# eight_neopixels.net
KiCad netlist of a schematic drawn in Altium Designer
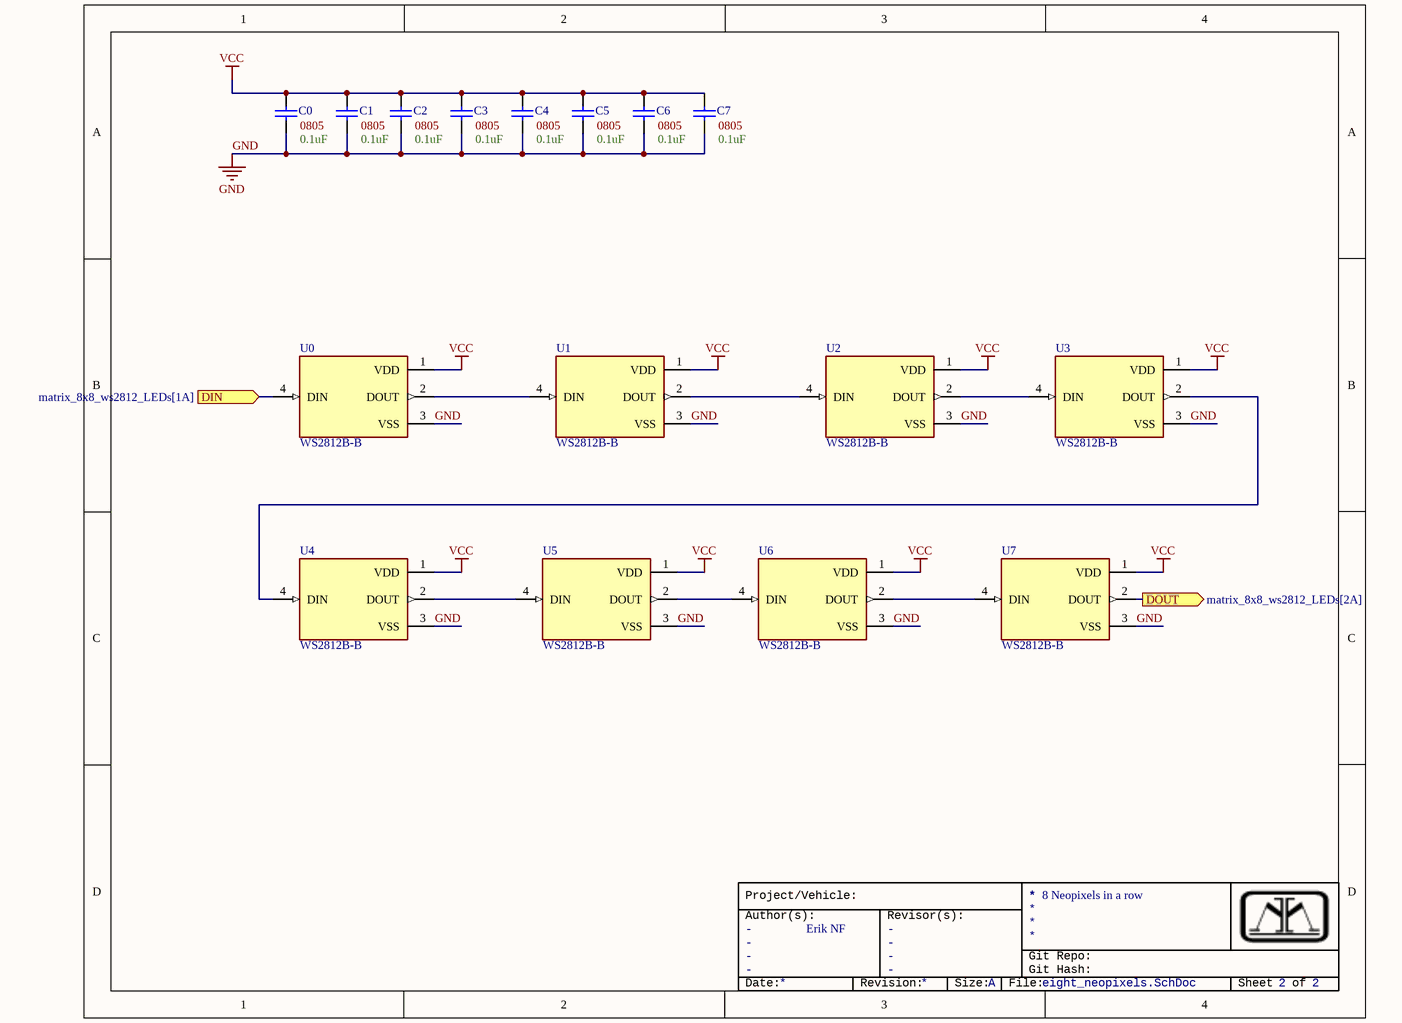
[diagram p0: eight_neopixels.SchDoc]

(export (version "E")
  (design (tool "Eeschema 10.0.6"))
  (components
    (comp (ref "C0")
      (value "SMD Nonpolarized")
      (footprint "[Cap] SMD 0805")
      (fields
        (field (name "VOLTAGE") "6.3V")
        (field (name "TOLERANCE") "10%")
        (field (name "SIZE PACKAGE") "0805")
        (field (name "CAPACITANCE") "0.1uF")
      )
      (libsource (lib "RADM Components") (part "[Cap] SMD Nonpolarized"))
    )
    (comp (ref "C1")
      (value "SMD Nonpolarized")
      (footprint "[Cap] SMD 0805")
      (fields
        (field (name "VOLTAGE") "6.3V")
        (field (name "TOLERANCE") "10%")
        (field (name "SIZE PACKAGE") "0805")
        (field (name "CAPACITANCE") "0.1uF")
      )
      (libsource (lib "RADM Components") (part "[Cap] SMD Nonpolarized"))
    )
    (comp (ref "C2")
      (value "SMD Nonpolarized")
      (footprint "[Cap] SMD 0805")
      (fields
        (field (name "VOLTAGE") "6.3V")
        (field (name "TOLERANCE") "10%")
        (field (name "SIZE PACKAGE") "0805")
        (field (name "CAPACITANCE") "0.1uF")
      )
      (libsource (lib "RADM Components") (part "[Cap] SMD Nonpolarized"))
    )
    (comp (ref "C3")
      (value "SMD Nonpolarized")
      (footprint "[Cap] SMD 0805")
      (fields
        (field (name "VOLTAGE") "6.3V")
        (field (name "TOLERANCE") "10%")
        (field (name "SIZE PACKAGE") "0805")
        (field (name "CAPACITANCE") "0.1uF")
      )
      (libsource (lib "RADM Components") (part "[Cap] SMD Nonpolarized"))
    )
    (comp (ref "C4")
      (value "SMD Nonpolarized")
      (footprint "[Cap] SMD 0805")
      (fields
        (field (name "VOLTAGE") "6.3V")
        (field (name "TOLERANCE") "10%")
        (field (name "SIZE PACKAGE") "0805")
        (field (name "CAPACITANCE") "0.1uF")
      )
      (libsource (lib "RADM Components") (part "[Cap] SMD Nonpolarized"))
    )
    (comp (ref "C5")
      (value "SMD Nonpolarized")
      (footprint "[Cap] SMD 0805")
      (fields
        (field (name "VOLTAGE") "6.3V")
        (field (name "TOLERANCE") "10%")
        (field (name "SIZE PACKAGE") "0805")
        (field (name "CAPACITANCE") "0.1uF")
      )
      (libsource (lib "RADM Components") (part "[Cap] SMD Nonpolarized"))
    )
    (comp (ref "C6")
      (value "SMD Nonpolarized")
      (footprint "[Cap] SMD 0805")
      (fields
        (field (name "VOLTAGE") "6.3V")
        (field (name "TOLERANCE") "10%")
        (field (name "SIZE PACKAGE") "0805")
        (field (name "CAPACITANCE") "0.1uF")
      )
      (libsource (lib "RADM Components") (part "[Cap] SMD Nonpolarized"))
    )
    (comp (ref "C7")
      (value "SMD Nonpolarized")
      (footprint "[Cap] SMD 0805")
      (fields
        (field (name "VOLTAGE") "6.3V")
        (field (name "TOLERANCE") "10%")
        (field (name "SIZE PACKAGE") "0805")
        (field (name "CAPACITANCE") "0.1uF")
      )
      (libsource (lib "RADM Components") (part "[Cap] SMD Nonpolarized"))
    )
    (comp (ref "U0")
      (value "WS2812B-B")
      (footprint "LED_WS2812B-B")
      (description "Intelligent control LED integrated light source")
      (libsource (lib "WS2812B-B") (part "WS2812B-B"))
    )
    (comp (ref "U1")
      (value "WS2812B-B")
      (footprint "LED_WS2812B-B")
      (description "Intelligent control LED integrated light source")
      (libsource (lib "WS2812B-B") (part "WS2812B-B"))
    )
    (comp (ref "U2")
      (value "WS2812B-B")
      (footprint "LED_WS2812B-B")
      (description "Intelligent control LED integrated light source")
      (libsource (lib "WS2812B-B") (part "WS2812B-B"))
    )
    (comp (ref "U3")
      (value "WS2812B-B")
      (footprint "LED_WS2812B-B")
      (description "Intelligent control LED integrated light source")
      (libsource (lib "WS2812B-B") (part "WS2812B-B"))
    )
    (comp (ref "U4")
      (value "WS2812B-B")
      (footprint "LED_WS2812B-B")
      (description "Intelligent control LED integrated light source")
      (libsource (lib "WS2812B-B") (part "WS2812B-B"))
    )
    (comp (ref "U5")
      (value "WS2812B-B")
      (footprint "LED_WS2812B-B")
      (description "Intelligent control LED integrated light source")
      (libsource (lib "WS2812B-B") (part "WS2812B-B"))
    )
    (comp (ref "U6")
      (value "WS2812B-B")
      (footprint "LED_WS2812B-B")
      (description "Intelligent control LED integrated light source")
      (libsource (lib "WS2812B-B") (part "WS2812B-B"))
    )
    (comp (ref "U7")
      (value "WS2812B-B")
      (footprint "LED_WS2812B-B")
      (description "Intelligent control LED integrated light source")
      (libsource (lib "WS2812B-B") (part "WS2812B-B"))
    )
  )
  (nets
    (net (code "1") (name "/DIN") (class "Default")
      (node (ref "U0") (pin "4") (pinfunction "DIN_4") (pintype "input"))
    )
    (net (code "2") (name "/DOUT") (class "Default")
      (node (ref "U7") (pin "2") (pinfunction "DOUT_2") (pintype "output"))
    )
    (net (code "3") (name "GND") (class "Default")
      (node (ref "C0") (pin "1") (pinfunction "1_1") (pintype "passive"))
      (node (ref "C1") (pin "1") (pinfunction "1_1") (pintype "passive"))
      (node (ref "C2") (pin "1") (pinfunction "1_1") (pintype "passive"))
      (node (ref "C3") (pin "1") (pinfunction "1_1") (pintype "passive"))
      (node (ref "C4") (pin "1") (pinfunction "1_1") (pintype "passive"))
      (node (ref "C5") (pin "1") (pinfunction "1_1") (pintype "passive"))
      (node (ref "C6") (pin "1") (pinfunction "1_1") (pintype "passive"))
      (node (ref "C7") (pin "1") (pinfunction "1_1") (pintype "passive"))
      (node (ref "U0") (pin "3") (pinfunction "VSS_3") (pintype "power_in"))
      (node (ref "U1") (pin "3") (pinfunction "VSS_3") (pintype "power_in"))
      (node (ref "U2") (pin "3") (pinfunction "VSS_3") (pintype "power_in"))
      (node (ref "U3") (pin "3") (pinfunction "VSS_3") (pintype "power_in"))
      (node (ref "U4") (pin "3") (pinfunction "VSS_3") (pintype "power_in"))
      (node (ref "U5") (pin "3") (pinfunction "VSS_3") (pintype "power_in"))
      (node (ref "U6") (pin "3") (pinfunction "VSS_3") (pintype "power_in"))
      (node (ref "U7") (pin "3") (pinfunction "VSS_3") (pintype "power_in"))
    )
    (net (code "4") (name "Net-(U0-DOUT)") (class "Default")
      (node (ref "U0") (pin "2") (pinfunction "DOUT_2") (pintype "output"))
      (node (ref "U1") (pin "4") (pinfunction "DIN_4") (pintype "input"))
    )
    (net (code "5") (name "Net-(U1-DOUT)") (class "Default")
      (node (ref "U1") (pin "2") (pinfunction "DOUT_2") (pintype "output"))
      (node (ref "U2") (pin "4") (pinfunction "DIN_4") (pintype "input"))
    )
    (net (code "6") (name "Net-(U2-DOUT)") (class "Default")
      (node (ref "U2") (pin "2") (pinfunction "DOUT_2") (pintype "output"))
      (node (ref "U3") (pin "4") (pinfunction "DIN_4") (pintype "input"))
    )
    (net (code "7") (name "Net-(U3-DOUT)") (class "Default")
      (node (ref "U3") (pin "2") (pinfunction "DOUT_2") (pintype "output"))
      (node (ref "U4") (pin "4") (pinfunction "DIN_4") (pintype "input"))
    )
    (net (code "8") (name "Net-(U4-DOUT)") (class "Default")
      (node (ref "U4") (pin "2") (pinfunction "DOUT_2") (pintype "output"))
      (node (ref "U5") (pin "4") (pinfunction "DIN_4") (pintype "input"))
    )
    (net (code "9") (name "Net-(U5-DOUT)") (class "Default")
      (node (ref "U5") (pin "2") (pinfunction "DOUT_2") (pintype "output"))
      (node (ref "U6") (pin "4") (pinfunction "DIN_4") (pintype "input"))
    )
    (net (code "10") (name "Net-(U6-DOUT)") (class "Default")
      (node (ref "U6") (pin "2") (pinfunction "DOUT_2") (pintype "output"))
      (node (ref "U7") (pin "4") (pinfunction "DIN_4") (pintype "input"))
    )
    (net (code "11") (name "VCC") (class "Default")
      (node (ref "C0") (pin "2") (pinfunction "2_2") (pintype "passive"))
      (node (ref "C1") (pin "2") (pinfunction "2_2") (pintype "passive"))
      (node (ref "C2") (pin "2") (pinfunction "2_2") (pintype "passive"))
      (node (ref "C3") (pin "2") (pinfunction "2_2") (pintype "passive"))
      (node (ref "C4") (pin "2") (pinfunction "2_2") (pintype "passive"))
      (node (ref "C5") (pin "2") (pinfunction "2_2") (pintype "passive"))
      (node (ref "C6") (pin "2") (pinfunction "2_2") (pintype "passive"))
      (node (ref "C7") (pin "2") (pinfunction "2_2") (pintype "passive"))
      (node (ref "U0") (pin "1") (pinfunction "VDD_1") (pintype "power_in"))
      (node (ref "U1") (pin "1") (pinfunction "VDD_1") (pintype "power_in"))
      (node (ref "U2") (pin "1") (pinfunction "VDD_1") (pintype "power_in"))
      (node (ref "U3") (pin "1") (pinfunction "VDD_1") (pintype "power_in"))
      (node (ref "U4") (pin "1") (pinfunction "VDD_1") (pintype "power_in"))
      (node (ref "U5") (pin "1") (pinfunction "VDD_1") (pintype "power_in"))
      (node (ref "U6") (pin "1") (pinfunction "VDD_1") (pintype "power_in"))
      (node (ref "U7") (pin "1") (pinfunction "VDD_1") (pintype "power_in"))
    )
  )
)
